# Sheet1.net
KiCad netlist of a schematic drawn in Altium Designer
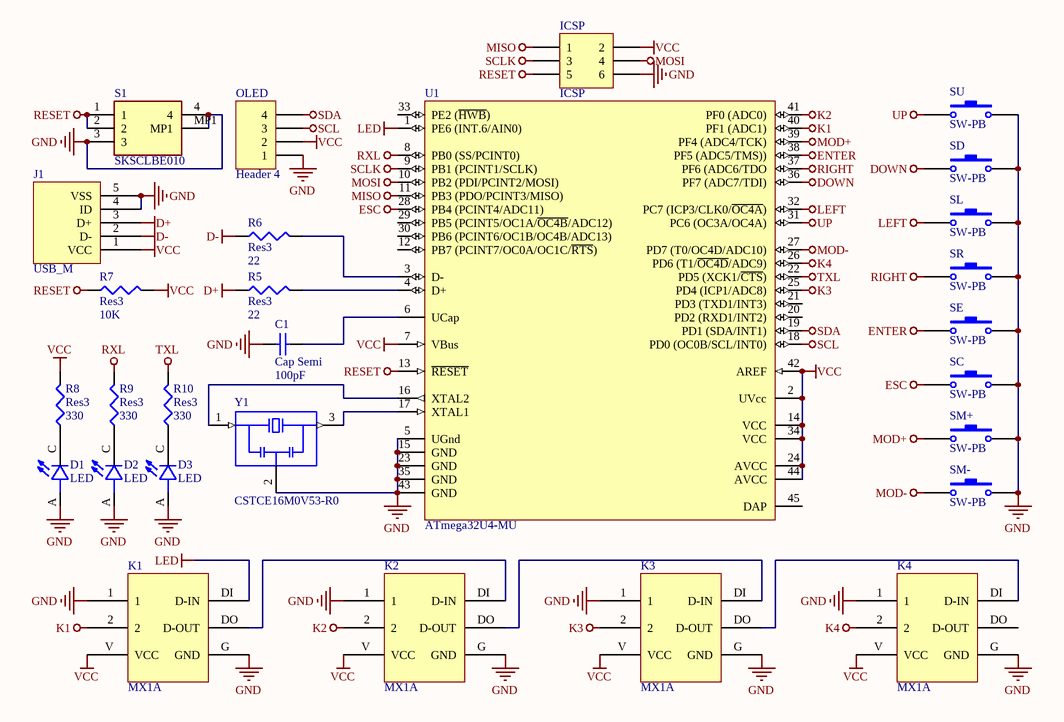
[diagram p0: Sheet1.SchDoc]

(export (version "E")
  (design (tool "Eeschema 10.0.6"))
  (components
    (comp (ref "C1")
      (value "Cap Semi")
      (footprint "1608[0603]")
      (description "Capacitor (Semiconductor SIM Model)")
      (fields (field (name "ALTIUM_VALUE") "100pF") (field (name "PUBLISHER") "Altium Limited"))
      (libsource (lib "Miscellaneous Devices") (part "Cap Semi"))
    )
    (comp (ref "D1")
      (value "LED")
      (footprint "LEDC1608X65N")
      (description "White LED Indication - Discrete 3.1V 0603 _1608 Metric_")
      (fields (field (name "MP") "LTW-C191TLA") (field (name "MF") "Lite-On"))
      (libsource (lib "LTW-C191TLA") (part "LTW-C191TLA"))
    )
    (comp (ref "D2")
      (value "LED")
      (footprint "LEDC1608X65N")
      (description "White LED Indication - Discrete 3.1V 0603 _1608 Metric_")
      (fields (field (name "MP") "LTW-C191TLA") (field (name "MF") "Lite-On"))
      (libsource (lib "LTW-C191TLA") (part "LTW-C191TLA"))
    )
    (comp (ref "D3")
      (value "LED")
      (footprint "LEDC1608X65N")
      (description "White LED Indication - Discrete 3.1V 0603 _1608 Metric_")
      (fields (field (name "MP") "LTW-C191TLA") (field (name "MF") "Lite-On"))
      (libsource (lib "LTW-C191TLA") (part "LTW-C191TLA"))
    )
    (comp (ref "ICSP")
      (value "ICSP")
      (footprint "HDR2X3")
      (description "Header, 3-Pin, Dual row")
      (fields (field (name "PUBLISHER") "Altium Limited"))
      (libsource (lib "Miscellaneous Connectors") (part "Header 3X2"))
    )
    (comp (ref "J1")
      (value "USB_M")
      (footprint "USB_MICRO")
      (description "MicroUSB諉諳")
      (libsource (lib "Fszhang") (part "USB_M"))
    )
    (comp (ref "K1") (value "MX1A") (footprint "MX1A") (libsource (lib "MX1A") (part "MX1A")))
    (comp (ref "K2") (value "MX1A") (footprint "MX1A") (libsource (lib "MX1A") (part "MX1A")))
    (comp (ref "K3") (value "MX1A") (footprint "MX1A") (libsource (lib "MX1A") (part "MX1A")))
    (comp (ref "K4") (value "MX1A") (footprint "MX1A") (libsource (lib "MX1A") (part "MX1A")))
    (comp (ref "OLED")
      (value "Header 4")
      (footprint "HDR1X4")
      (description "Header, 4-Pin")
      (fields (field (name "PUBLISHER") "Altium Limited"))
      (libsource (lib "Miscellaneous Connectors") (part "Header 4"))
    )
    (comp (ref "R5")
      (value "Res3")
      (footprint "J1-0603")
      (description "Resistor")
      (fields (field (name "ALTIUM_VALUE") "22") (field (name "PUBLISHER") "Altium Limited"))
      (libsource (lib "Miscellaneous Devices") (part "Res3"))
    )
    (comp (ref "R6")
      (value "Res3")
      (footprint "J1-0603")
      (description "Resistor")
      (fields (field (name "ALTIUM_VALUE") "22") (field (name "PUBLISHER") "Altium Limited"))
      (libsource (lib "Miscellaneous Devices") (part "Res3"))
    )
    (comp (ref "R7")
      (value "Res3")
      (footprint "J1-0603")
      (description "Resistor")
      (fields (field (name "ALTIUM_VALUE") "10K") (field (name "PUBLISHER") "Altium Limited"))
      (libsource (lib "Miscellaneous Devices") (part "Res3"))
    )
    (comp (ref "R8")
      (value "Res3")
      (footprint "J1-0603")
      (description "Resistor")
      (fields (field (name "ALTIUM_VALUE") "330") (field (name "PUBLISHER") "Altium Limited"))
      (libsource (lib "Miscellaneous Devices") (part "Res3"))
    )
    (comp (ref "R9")
      (value "Res3")
      (footprint "J1-0603")
      (description "Resistor")
      (fields (field (name "ALTIUM_VALUE") "330") (field (name "PUBLISHER") "Altium Limited"))
      (libsource (lib "Miscellaneous Devices") (part "Res3"))
    )
    (comp (ref "R10")
      (value "Res3")
      (footprint "J1-0603")
      (description "Resistor")
      (fields (field (name "ALTIUM_VALUE") "330") (field (name "PUBLISHER") "Altium Limited"))
      (libsource (lib "Miscellaneous Devices") (part "Res3"))
    )
    (comp (ref "S1")
      (value "SKSCLBE010")
      (footprint "SKSCLBE010")
      (description "Switch")
      (libsource (lib "SKSCLBE010 小烏龜") (part "SKSCLBE010"))
    )
    (comp (ref "SC")
      (value "SW-PB")
      (footprint "SW_PB2_B1")
      (description "峚雄羲壽")
      (fields (field (name "PUBLISHER") "Altium Limited"))
      (libsource (lib "Fszhang") (part "SW-PB"))
    )
    (comp (ref "SD")
      (value "SW-PB")
      (footprint "SW_PB2_B1")
      (description "峚雄羲壽")
      (fields (field (name "PUBLISHER") "Altium Limited"))
      (libsource (lib "Fszhang") (part "SW-PB"))
    )
    (comp (ref "SE")
      (value "SW-PB")
      (footprint "SW_PB2_B1")
      (description "峚雄羲壽")
      (fields (field (name "PUBLISHER") "Altium Limited"))
      (libsource (lib "Fszhang") (part "SW-PB"))
    )
    (comp (ref "SL")
      (value "SW-PB")
      (footprint "SW_PB2_B1")
      (description "峚雄羲壽")
      (fields (field (name "PUBLISHER") "Altium Limited"))
      (libsource (lib "Fszhang") (part "SW-PB"))
    )
    (comp (ref "SM+")
      (value "SW-PB")
      (footprint "SW_PB2_B1")
      (description "峚雄羲壽")
      (fields (field (name "PUBLISHER") "Altium Limited"))
      (libsource (lib "Fszhang") (part "SW-PB"))
    )
    (comp (ref "SM-")
      (value "SW-PB")
      (footprint "SW_PB2_B1")
      (description "峚雄羲壽")
      (fields (field (name "PUBLISHER") "Altium Limited"))
      (libsource (lib "Fszhang") (part "SW-PB"))
    )
    (comp (ref "SR")
      (value "SW-PB")
      (footprint "SW_PB2_B1")
      (description "峚雄羲壽")
      (fields (field (name "PUBLISHER") "Altium Limited"))
      (libsource (lib "Fszhang") (part "SW-PB"))
    )
    (comp (ref "SU")
      (value "SW-PB")
      (footprint "SW_PB2_B1")
      (description "峚雄羲壽")
      (fields (field (name "PUBLISHER") "Altium Limited"))
      (libsource (lib "Fszhang") (part "SW-PB"))
    )
    (comp (ref "U1")
      (value "ATmega32U4-MU")
      (footprint "44PW_N")
      (fields (field (name "PUBLISHER") "Altium Limited"))
      (libsource (lib "Atmel Microcontroller 8-Bit megaAVR") (part "ATmega32U4-MU"))
    )
    (comp (ref "Y1")
      (value "CSTCE16M0V53-R0")
      (footprint "OSC_CSTCE16M0V53-R0")
      (description "16MHz Ceramic Resonator Built in Capacitor 15pF Â±0.3% -20Â°C ~ 80Â°C Surface Mount")
      (fields (field (name "MF") "Murata"))
      (libsource (lib "CSTCE16M0V53-R0") (part "CSTCE16M0V53-R0"))
    )
  )
  (nets
    (net (code "1") (name "D+") (class "Default")
      (node (ref "J1") (pin "3") (pinfunction "D+_3") (pintype "passive"))
      (node (ref "R5") (pin "1") (pinfunction "1_1") (pintype "passive"))
    )
    (net (code "2") (name "D-") (class "Default")
      (node (ref "J1") (pin "2") (pinfunction "D-_2") (pintype "passive"))
      (node (ref "R6") (pin "1") (pinfunction "1_1") (pintype "passive"))
    )
    (net (code "3") (name "DOWN") (class "Default")
      (node (ref "SD") (pin "1") (pinfunction "1_1") (pintype "passive"))
      (node (ref "U1") (pin "36") (pinfunction "PF7_(ADC7/TDI)_36") (pintype "bidirectional"))
    )
    (net (code "4") (name "ENTER") (class "Default")
      (node (ref "SE") (pin "1") (pinfunction "1_1") (pintype "passive"))
      (node (ref "U1") (pin "38") (pinfunction "PF5_(ADC5/TMS))_38") (pintype "bidirectional"))
    )
    (net (code "5") (name "ESC") (class "Default")
      (node (ref "SC") (pin "1") (pinfunction "1_1") (pintype "passive"))
      (node (ref "U1") (pin "28") (pinfunction "PB4_(PCINT4/ADC11)_28") (pintype "bidirectional"))
    )
    (net (code "6") (name "GND") (class "Default")
      (node (ref "C1") (pin "1") (pinfunction "1_1") (pintype "passive"))
      (node (ref "D1") (pin "A") (pinfunction "A_A") (pintype "passive"))
      (node (ref "D2") (pin "A") (pinfunction "A_A") (pintype "passive"))
      (node (ref "D3") (pin "A") (pinfunction "A_A") (pintype "passive"))
      (node (ref "ICSP") (pin "6") (pinfunction "6_6") (pintype "passive"))
      (node (ref "J1") (pin "4") (pinfunction "ID_4") (pintype "passive"))
      (node (ref "J1") (pin "5") (pinfunction "VSS_5") (pintype "passive"))
      (node (ref "K1") (pin "1") (pinfunction "1_1") (pintype "passive"))
      (node (ref "K1") (pin "G") (pinfunction "GND_G") (pintype "passive"))
      (node (ref "K2") (pin "1") (pinfunction "1_1") (pintype "passive"))
      (node (ref "K2") (pin "G") (pinfunction "GND_G") (pintype "passive"))
      (node (ref "K3") (pin "1") (pinfunction "1_1") (pintype "passive"))
      (node (ref "K3") (pin "G") (pinfunction "GND_G") (pintype "passive"))
      (node (ref "K4") (pin "1") (pinfunction "1_1") (pintype "passive"))
      (node (ref "K4") (pin "G") (pinfunction "GND_G") (pintype "passive"))
      (node (ref "OLED") (pin "1") (pinfunction "1_1") (pintype "passive"))
      (node (ref "S1") (pin "3") (pinfunction "3_3") (pintype "passive"))
      (node (ref "S1") (pin "4") (pinfunction "4_4") (pintype "passive"))
      (node (ref "S1") (pin "MP1") (pinfunction "MP1_MP1") (pintype "passive"))
      (node (ref "SC") (pin "2") (pinfunction "2_2") (pintype "passive"))
      (node (ref "SD") (pin "2") (pinfunction "2_2") (pintype "passive"))
      (node (ref "SE") (pin "2") (pinfunction "2_2") (pintype "passive"))
      (node (ref "SL") (pin "2") (pinfunction "2_2") (pintype "passive"))
      (node (ref "SM+") (pin "2") (pinfunction "2_2") (pintype "passive"))
      (node (ref "SM-") (pin "2") (pinfunction "2_2") (pintype "passive"))
      (node (ref "SR") (pin "2") (pinfunction "2_2") (pintype "passive"))
      (node (ref "SU") (pin "2") (pinfunction "2_2") (pintype "passive"))
      (node (ref "U1") (pin "15") (pinfunction "GND_15") (pintype "power_in"))
      (node (ref "U1") (pin "23") (pinfunction "GND_23") (pintype "power_in"))
      (node (ref "U1") (pin "35") (pinfunction "GND_35") (pintype "power_in"))
      (node (ref "U1") (pin "43") (pinfunction "GND_43") (pintype "power_in"))
      (node (ref "U1") (pin "5") (pinfunction "UGnd_5") (pintype "power_in"))
      (node (ref "Y1") (pin "2") (pinfunction "GND_2") (pintype "power_in"))
    )
    (net (code "7") (name "K1") (class "Default")
      (node (ref "K1") (pin "2") (pinfunction "2_2") (pintype "passive"))
      (node (ref "U1") (pin "40") (pinfunction "PF1_(ADC1)_40") (pintype "bidirectional"))
    )
    (net (code "8") (name "K2") (class "Default")
      (node (ref "K2") (pin "2") (pinfunction "2_2") (pintype "passive"))
      (node (ref "U1") (pin "41") (pinfunction "PF0_(ADC0)_41") (pintype "bidirectional"))
    )
    (net (code "9") (name "K3") (class "Default")
      (node (ref "K3") (pin "2") (pinfunction "2_2") (pintype "passive"))
      (node (ref "U1") (pin "25") (pinfunction "PD4_(ICP1/ADC8)_25") (pintype "bidirectional"))
    )
    (net (code "10") (name "K4") (class "Default")
      (node (ref "K4") (pin "2") (pinfunction "2_2") (pintype "passive"))
      (node (ref "U1") (pin "26") (pinfunction "PD6_(T1/~{OC4D}/ADC9)_26") (pintype "bidirectional"))
    )
    (net (code "11") (name "LED") (class "Default")
      (node (ref "K1") (pin "DI") (pinfunction "D-IN_DI") (pintype "passive"))
      (node (ref "U1") (pin "1") (pinfunction "PE6_(INT.6/AIN0)_1") (pintype "bidirectional"))
    )
    (net (code "12") (name "LEFT") (class "Default")
      (node (ref "SL") (pin "1") (pinfunction "1_1") (pintype "passive"))
      (node (ref "U1") (pin "32") (pinfunction "PC7_(ICP3/CLK0/~{OC4A})_32") (pintype "bidirectional"))
    )
    (net (code "13") (name "MISO") (class "Default")
      (node (ref "ICSP") (pin "1") (pinfunction "1_1") (pintype "passive"))
      (node (ref "U1") (pin "11") (pinfunction "PB3_(PDO/PCINT3/MISO)_11") (pintype "bidirectional"))
    )
    (net (code "14") (name "MOD+") (class "Default")
      (node (ref "SM+") (pin "1") (pinfunction "1_1") (pintype "passive"))
      (node (ref "U1") (pin "39") (pinfunction "PF4_(ADC4/TCK)_39") (pintype "bidirectional"))
    )
    (net (code "15") (name "MOD-") (class "Default")
      (node (ref "SM-") (pin "1") (pinfunction "1_1") (pintype "passive"))
      (node (ref "U1") (pin "27") (pinfunction "PD7_(T0/OC4D/ADC10)_27") (pintype "bidirectional"))
    )
    (net (code "16") (name "MOSI") (class "Default")
      (node (ref "ICSP") (pin "4") (pinfunction "4_4") (pintype "passive"))
      (node (ref "U1") (pin "10") (pinfunction "PB2_(PDI/PCINT2/MOSI)_10") (pintype "bidirectional"))
    )
    (net (code "17") (name "Net-(D1-PadC)") (class "Default")
      (node (ref "D1") (pin "C") (pinfunction "C_C") (pintype "passive"))
      (node (ref "R8") (pin "1") (pinfunction "1_1") (pintype "passive"))
    )
    (net (code "18") (name "Net-(D2-PadC)") (class "Default")
      (node (ref "D2") (pin "C") (pinfunction "C_C") (pintype "passive"))
      (node (ref "R9") (pin "1") (pinfunction "1_1") (pintype "passive"))
    )
    (net (code "19") (name "Net-(D3-PadC)") (class "Default")
      (node (ref "D3") (pin "C") (pinfunction "C_C") (pintype "passive"))
      (node (ref "R10") (pin "1") (pinfunction "1_1") (pintype "passive"))
    )
    (net (code "20") (name "Net-(K1-D-OUT)") (class "Default")
      (node (ref "K1") (pin "DO") (pinfunction "D-OUT_DO") (pintype "passive"))
      (node (ref "K2") (pin "DI") (pinfunction "D-IN_DI") (pintype "passive"))
    )
    (net (code "21") (name "Net-(K2-D-OUT)") (class "Default")
      (node (ref "K2") (pin "DO") (pinfunction "D-OUT_DO") (pintype "passive"))
      (node (ref "K3") (pin "DI") (pinfunction "D-IN_DI") (pintype "passive"))
    )
    (net (code "22") (name "Net-(K3-D-OUT)") (class "Default")
      (node (ref "K3") (pin "DO") (pinfunction "D-OUT_DO") (pintype "passive"))
      (node (ref "K4") (pin "DI") (pinfunction "D-IN_DI") (pintype "passive"))
    )
    (net (code "23") (name "Net-(U1-D+)") (class "Default")
      (node (ref "R5") (pin "2") (pinfunction "2_2") (pintype "passive"))
      (node (ref "U1") (pin "4") (pinfunction "D+_4") (pintype "bidirectional"))
    )
    (net (code "24") (name "Net-(U1-D-)") (class "Default")
      (node (ref "R6") (pin "2") (pinfunction "2_2") (pintype "passive"))
      (node (ref "U1") (pin "3") (pinfunction "D-_3") (pintype "bidirectional"))
    )
    (net (code "25") (name "Net-(U1-UCap)") (class "Default")
      (node (ref "C1") (pin "2") (pinfunction "2_2") (pintype "passive"))
      (node (ref "U1") (pin "6") (pinfunction "UCap_6") (pintype "passive"))
    )
    (net (code "26") (name "Net-(U1-XTAL1)") (class "Default")
      (node (ref "U1") (pin "17") (pinfunction "XTAL1_17") (pintype "input"))
      (node (ref "Y1") (pin "3") (pinfunction "OUT_3") (pintype "output"))
    )
    (net (code "27") (name "Net-(U1-XTAL2)") (class "Default")
      (node (ref "U1") (pin "16") (pinfunction "XTAL2_16") (pintype "output"))
      (node (ref "Y1") (pin "1") (pinfunction "IN_1") (pintype "input"))
    )
    (net (code "28") (name "RESET") (class "Default")
      (node (ref "ICSP") (pin "5") (pinfunction "5_5") (pintype "passive"))
      (node (ref "R7") (pin "1") (pinfunction "1_1") (pintype "passive"))
      (node (ref "S1") (pin "1") (pinfunction "1_1") (pintype "passive"))
      (node (ref "S1") (pin "2") (pinfunction "2_2") (pintype "passive"))
      (node (ref "U1") (pin "13") (pinfunction "~{RESET}_13") (pintype "input"))
    )
    (net (code "29") (name "RIGHT") (class "Default")
      (node (ref "SR") (pin "1") (pinfunction "1_1") (pintype "passive"))
      (node (ref "U1") (pin "37") (pinfunction "PF6_(ADC6/TDO_37") (pintype "bidirectional"))
    )
    (net (code "30") (name "RXL") (class "Default")
      (node (ref "R9") (pin "2") (pinfunction "2_2") (pintype "passive"))
      (node (ref "U1") (pin "8") (pinfunction "PB0_(SS/PCINT0)_8") (pintype "bidirectional"))
    )
    (net (code "31") (name "SCL") (class "Default")
      (node (ref "OLED") (pin "3") (pinfunction "3_3") (pintype "passive"))
      (node (ref "U1") (pin "18") (pinfunction "PD0_(OC0B/SCL/INT0)_18") (pintype "bidirectional"))
    )
    (net (code "32") (name "SCLK") (class "Default")
      (node (ref "ICSP") (pin "3") (pinfunction "3_3") (pintype "passive"))
      (node (ref "U1") (pin "9") (pinfunction "PB1_(PCINT1/SCLK)_9") (pintype "bidirectional"))
    )
    (net (code "33") (name "SDA") (class "Default")
      (node (ref "OLED") (pin "4") (pinfunction "4_4") (pintype "passive"))
      (node (ref "U1") (pin "19") (pinfunction "PD1_(SDA/INT1)_19") (pintype "bidirectional"))
    )
    (net (code "34") (name "TXL") (class "Default")
      (node (ref "R10") (pin "2") (pinfunction "2_2") (pintype "passive"))
      (node (ref "U1") (pin "22") (pinfunction "PD5_(XCK1/~{CTS})_22") (pintype "bidirectional"))
    )
    (net (code "35") (name "UP") (class "Default")
      (node (ref "SU") (pin "1") (pinfunction "1_1") (pintype "passive"))
      (node (ref "U1") (pin "31") (pinfunction "PC6_(OC3A/OC4A)_31") (pintype "bidirectional"))
    )
    (net (code "36") (name "VCC") (class "Default")
      (node (ref "ICSP") (pin "2") (pinfunction "2_2") (pintype "passive"))
      (node (ref "J1") (pin "1") (pinfunction "VCC_1") (pintype "passive"))
      (node (ref "K1") (pin "V") (pinfunction "VCC_V") (pintype "passive"))
      (node (ref "K2") (pin "V") (pinfunction "VCC_V") (pintype "passive"))
      (node (ref "K3") (pin "V") (pinfunction "VCC_V") (pintype "passive"))
      (node (ref "K4") (pin "V") (pinfunction "VCC_V") (pintype "passive"))
      (node (ref "OLED") (pin "2") (pinfunction "2_2") (pintype "passive"))
      (node (ref "R7") (pin "2") (pinfunction "2_2") (pintype "passive"))
      (node (ref "R8") (pin "2") (pinfunction "2_2") (pintype "passive"))
      (node (ref "U1") (pin "14") (pinfunction "VCC_14") (pintype "power_in"))
      (node (ref "U1") (pin "2") (pinfunction "UVcc_2") (pintype "power_in"))
      (node (ref "U1") (pin "24") (pinfunction "AVCC_24") (pintype "power_in"))
      (node (ref "U1") (pin "34") (pinfunction "VCC_34") (pintype "power_in"))
      (node (ref "U1") (pin "42") (pinfunction "AREF_42") (pintype "input"))
      (node (ref "U1") (pin "44") (pinfunction "AVCC_44") (pintype "power_in"))
      (node (ref "U1") (pin "7") (pinfunction "VBus_7") (pintype "input"))
    )
    (net (code "37") (name "unconnected-(K4-D-OUT-PadDO)") (class "Default")
      (node (ref "K4") (pin "DO") (pinfunction "D-OUT_DO") (pintype "passive"))
    )
    (net (code "38") (name "unconnected-(U1-DAP-Pad45)") (class "Default")
      (node (ref "U1") (pin "45") (pinfunction "DAP_45") (pintype "power_in"))
    )
    (net (code "39") (name "unconnected-(U1-PB5_(PCINT5{slash}OC1A{slash}~{OC4B}{slash}ADC12)-Pad29)") (class "Default")
      (node (ref "U1") (pin "29") (pinfunction "PB5_(PCINT5/OC1A/~{OC4B}/ADC12)_29") (pintype "bidirectional"))
    )
    (net (code "40") (name "unconnected-(U1-PB6_(PCINT6{slash}OC1B{slash}OC4B{slash}ADC13)-Pad30)") (class "Default")
      (node (ref "U1") (pin "30") (pinfunction "PB6_(PCINT6/OC1B/OC4B/ADC13)_30") (pintype "bidirectional"))
    )
    (net (code "41") (name "unconnected-(U1-PB7_(PCINT7{slash}OC0A{slash}OC1C{slash}~{RTS})-Pad12)") (class "Default")
      (node (ref "U1") (pin "12") (pinfunction "PB7_(PCINT7/OC0A/OC1C/~{RTS})_12") (pintype "bidirectional"))
    )
    (net (code "42") (name "unconnected-(U1-PD2_(RXD1{slash}INT2)-Pad20)") (class "Default")
      (node (ref "U1") (pin "20") (pinfunction "PD2_(RXD1/INT2)_20") (pintype "bidirectional"))
    )
    (net (code "43") (name "unconnected-(U1-PD3_(TXD1{slash}INT3)-Pad21)") (class "Default")
      (node (ref "U1") (pin "21") (pinfunction "PD3_(TXD1/INT3)_21") (pintype "bidirectional"))
    )
    (net (code "44") (name "unconnected-(U1-PE2_(~{HWB})-Pad33)") (class "Default")
      (node (ref "U1") (pin "33") (pinfunction "PE2_(~{HWB})_33") (pintype "bidirectional"))
    )
  )
)
